# MODULE.net
KiCad netlist of a schematic drawn in Altium Designer
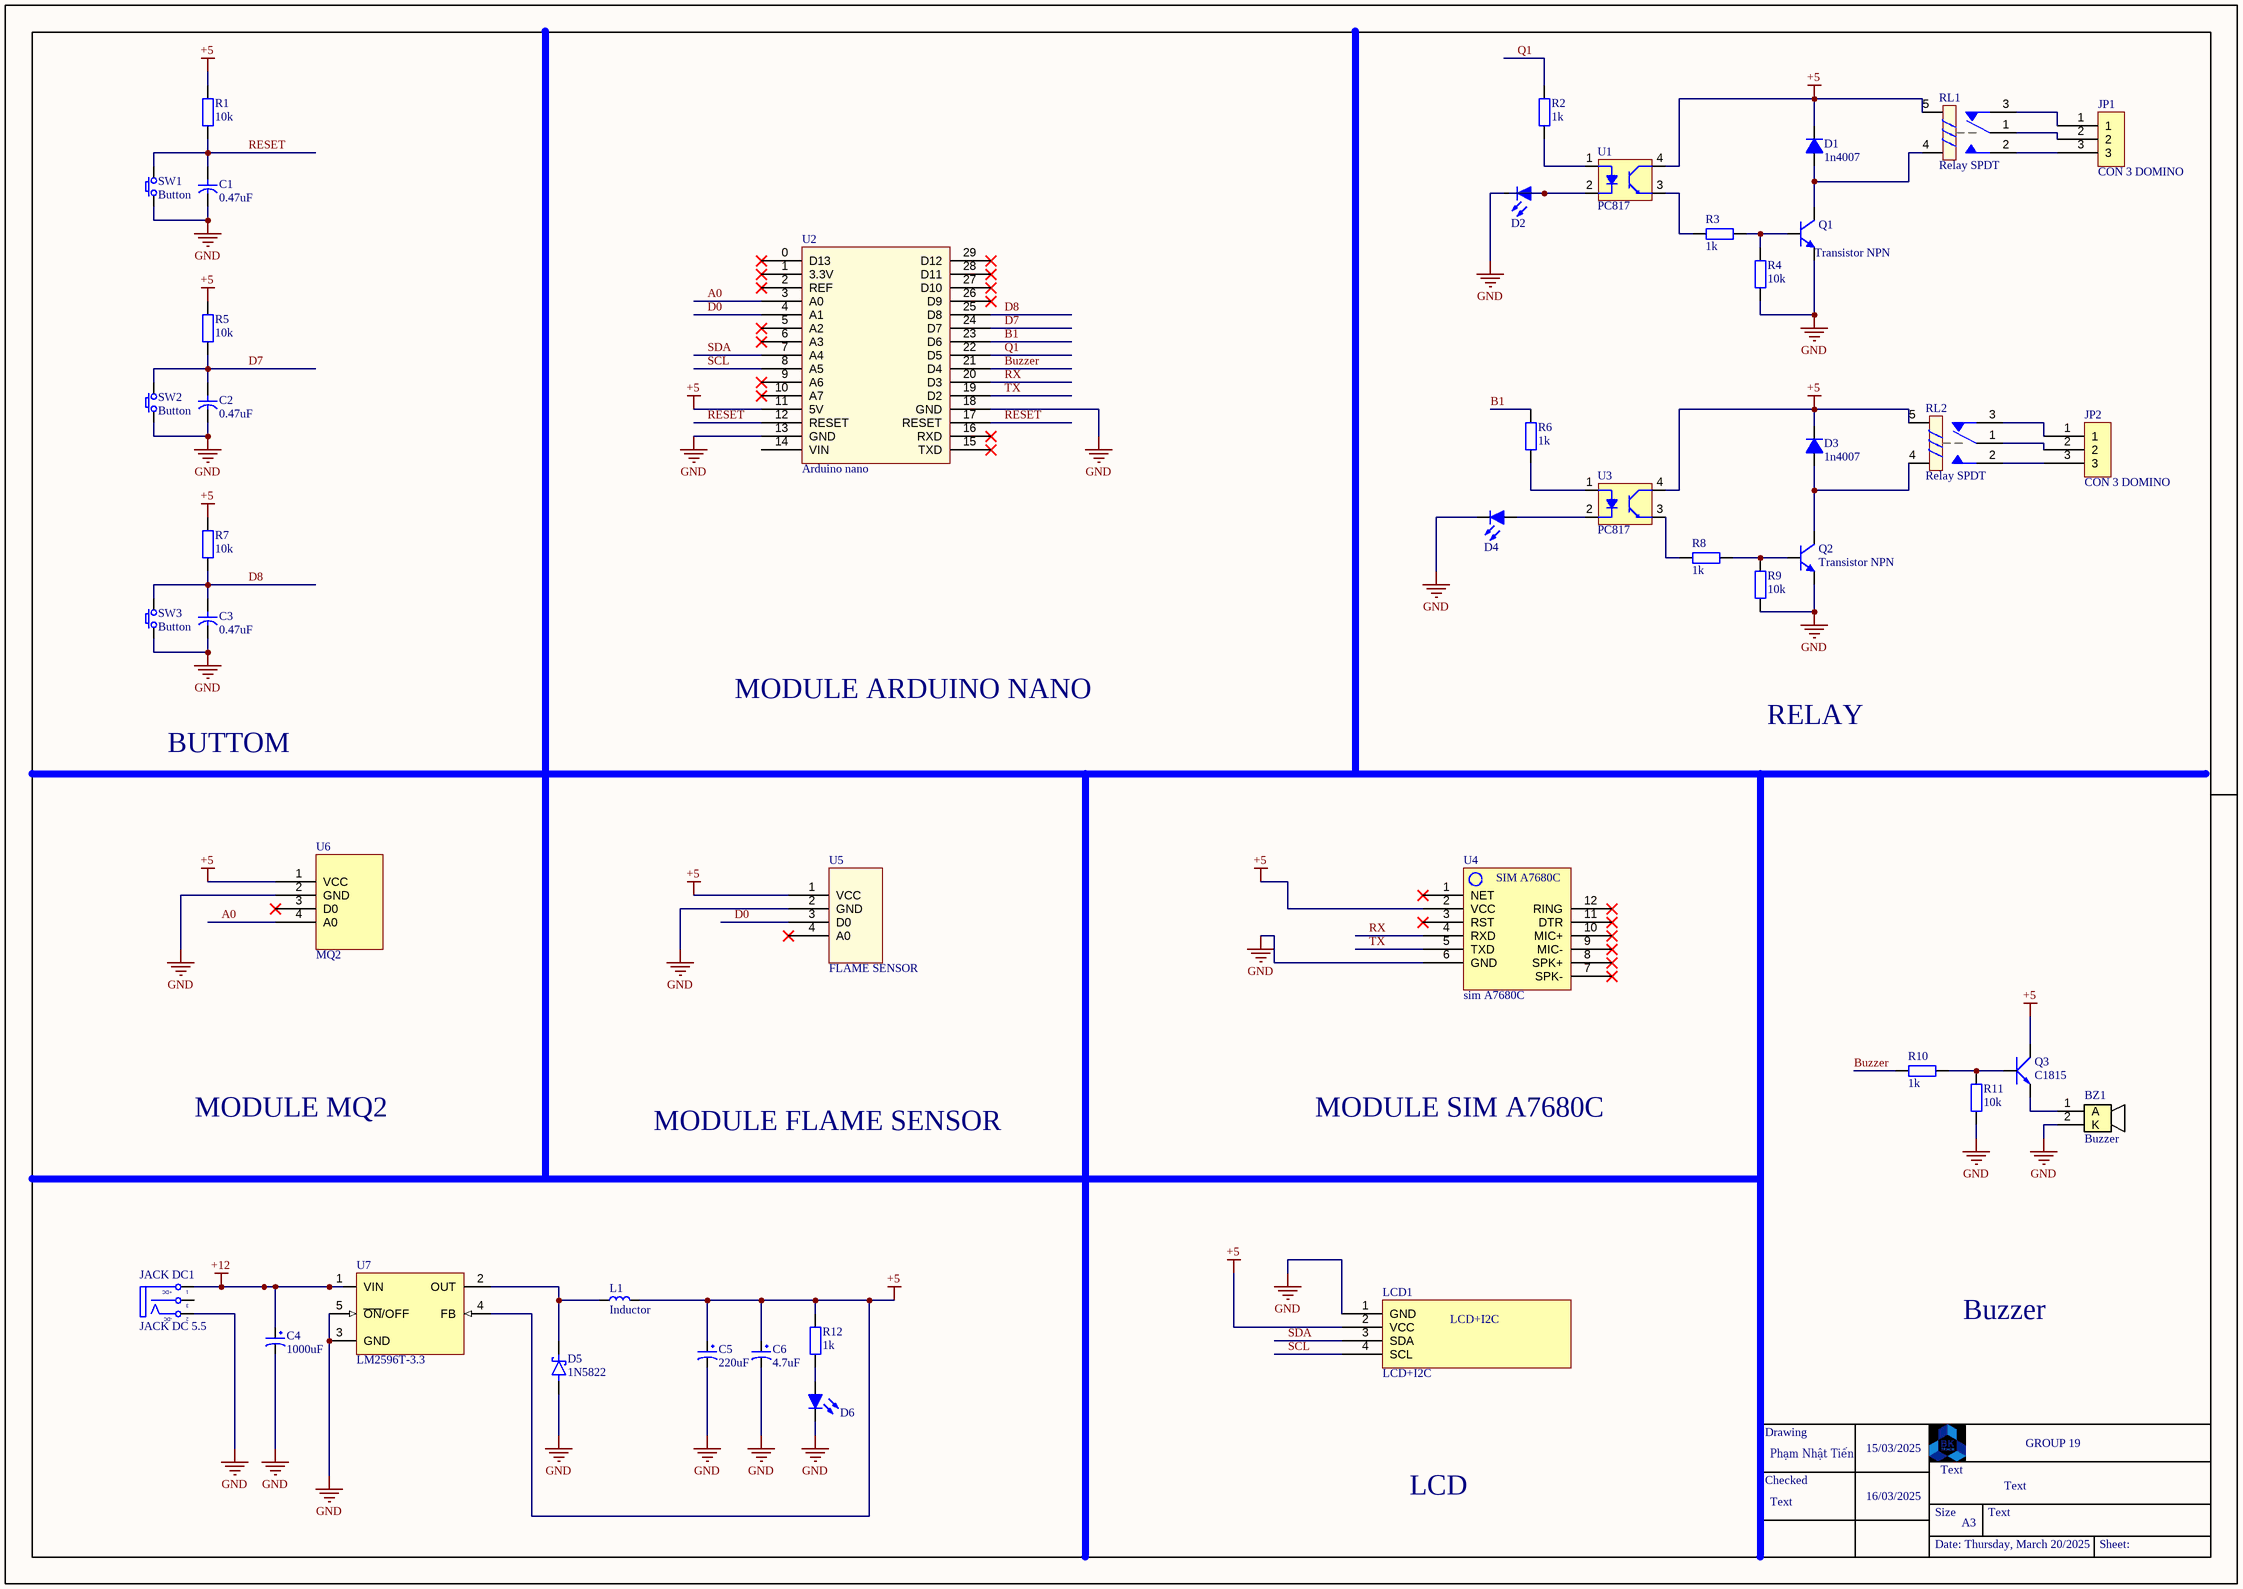
[diagram p0: MODULE.SchDoc]

(export (version "E")
  (design (tool "Eeschema 10.0.6"))
  (components
    (comp (ref "BZ1")
      (value "Buzzer")
      (footprint "BUZZER-2")
      (libsource (lib "chipfc_altium_libs") (part "Buzzer"))
    )
    (comp (ref "C1")
      (value "0.47uF")
      (footprint "CYL/D.250/LS.100")
      (description "Capacitor pol")
      (libsource (lib "chipfc_altium_libs") (part "Capacitor"))
    )
    (comp (ref "C2")
      (value "0.47uF")
      (footprint "CYL/D.250/LS.100")
      (description "Capacitor pol")
      (libsource (lib "chipfc_altium_libs") (part "Capacitor"))
    )
    (comp (ref "C3")
      (value "0.47uF")
      (footprint "CYL/D.250/LS.100")
      (description "Capacitor pol")
      (libsource (lib "chipfc_altium_libs") (part "Capacitor"))
    )
    (comp (ref "C4")
      (value "1000uF")
      (footprint "tu hoa 13mm")
      (description "Cắm")
      (libsource (lib "Altium_Lib_by_KhueNguyenCreator") (part "Tu Hoa 1000uF 50V 13x26"))
    )
    (comp (ref "C5")
      (value "220uF")
      (footprint "tu hoa 10mm")
      (description "Cắm")
      (libsource (lib "Altium_Lib_by_KhueNguyenCreator") (part "Tu Hoa 220uF 50V 10x14"))
    )
    (comp (ref "C6")
      (value "4.7uF")
      (footprint "tu hoa 5mm")
      (description "Cắm")
      (libsource (lib "Altium_Lib_by_KhueNguyenCreator") (part "Tu Hoa 0.47uF 50V 5x11"))
    )
    (comp (ref "D1")
      (value "1n4007")
      (footprint "DIODE 1A")
      (description "Cắm")
      (libsource (lib "Altium_Lib_by_KhueNguyenCreator") (part "Diode 1N4007"))
    )
    (comp (ref "D2")
      (value "Led")
      (footprint "LED 5MM - RED")
      (description "Typical LED")
      (libsource (lib "chipfc_altium_libs") (part "Led"))
    )
    (comp (ref "D3")
      (value "1n4007")
      (footprint "DIODE 1A")
      (description "Cắm")
      (libsource (lib "Altium_Lib_by_KhueNguyenCreator") (part "Diode 1N4007"))
    )
    (comp (ref "D4")
      (value "Led")
      (footprint "LED 5MM - RED")
      (description "Typical LED")
      (libsource (lib "chipfc_altium_libs") (part "Led"))
    )
    (comp (ref "D5") (value "1N5822") (footprint "1N5822") (libsource (lib "TIEN") (part "1N5822")))
    (comp (ref "D6")
      (value "Led")
      (footprint "LED 5MM - RED")
      (description "Typical LED")
      (libsource (lib "chipfc_altium_libs") (part "Led"))
    )
    (comp (ref "JACK DC1")
      (value "JACK DC 5.5")
      (footprint "JACK DC 5.5")
      (libsource (lib "Altium_Lib_by_KhueNguyenCreator") (part "JACK DC 5.5"))
    )
    (comp (ref "JP1")
      (value "CON 3 DOMINO")
      (footprint "CON 3")
      (libsource (lib "TIEN") (part "CON 3 DOMINO"))
    )
    (comp (ref "JP2")
      (value "CON 3 DOMINO")
      (footprint "CON 3")
      (libsource (lib "TIEN") (part "CON 3 DOMINO"))
    )
    (comp (ref "L1")
      (value "Inductor")
      (footprint "L/D9H12")
      (libsource (lib "chipfc_altium_libs") (part "Inductor"))
    )
    (comp (ref "LCD1") (value "LCD+I2C") (footprint "LCD+I2C") (libsource (lib "TIEN") (part "LCD+I2C")))
    (comp (ref "Q1")
      (value "Transistor NPN")
      (footprint "TO-92/W100")
      (description "NPN Bipolar Transistor")
      (libsource (lib "chipfc_altium_libs") (part "Transistor NPN"))
    )
    (comp (ref "Q2")
      (value "Transistor NPN")
      (footprint "TO-92/W100")
      (description "NPN Bipolar Transistor")
      (libsource (lib "chipfc_altium_libs") (part "Transistor NPN"))
    )
    (comp (ref "Q3")
      (value "C1815")
      (footprint "TO92")
      (description "NPN transistor")
      (libsource (lib "Altium_Lib_by_KhueNguyenCreator") (part "Trans C1815 DIP"))
    )
    (comp (ref "R1")
      (value "10k")
      (footprint "tro vach 1/4w")
      (description "Căm")
      (libsource (lib "Altium_Lib_by_KhueNguyenCreator") (part "Tro Vach 1/4W 5% 10k"))
    )
    (comp (ref "R2")
      (value "1k")
      (footprint "tro vach 1/4w")
      (description "Cắm")
      (libsource (lib "Altium_Lib_by_KhueNguyenCreator") (part "Tro Vach 1/4W 5% 1k"))
    )
    (comp (ref "R3")
      (value "1k")
      (footprint "tro vach 1/4w")
      (description "Cắm")
      (libsource (lib "Altium_Lib_by_KhueNguyenCreator") (part "Tro Vach 1/4W 5% 1k"))
    )
    (comp (ref "R4")
      (value "10k")
      (footprint "tro vach 1/4w")
      (description "Cắm")
      (libsource (lib "Altium_Lib_by_KhueNguyenCreator") (part "Tro Vach 1/4W 1% 10k"))
    )
    (comp (ref "R5")
      (value "10k")
      (footprint "tro vach 1/4w")
      (description "Căm")
      (libsource (lib "Altium_Lib_by_KhueNguyenCreator") (part "Tro Vach 1/4W 5% 10k"))
    )
    (comp (ref "R6")
      (value "1k")
      (footprint "tro vach 1/4w")
      (description "Cắm")
      (libsource (lib "Altium_Lib_by_KhueNguyenCreator") (part "Tro Vach 1/4W 5% 1k"))
    )
    (comp (ref "R7")
      (value "10k")
      (footprint "tro vach 1/4w")
      (description "Căm")
      (libsource (lib "Altium_Lib_by_KhueNguyenCreator") (part "Tro Vach 1/4W 5% 10k"))
    )
    (comp (ref "R8")
      (value "1k")
      (footprint "tro vach 1/4w")
      (description "Cắm")
      (libsource (lib "Altium_Lib_by_KhueNguyenCreator") (part "Tro Vach 1/4W 5% 1k"))
    )
    (comp (ref "R9")
      (value "10k")
      (footprint "tro vach 1/4w")
      (description "Cắm")
      (libsource (lib "Altium_Lib_by_KhueNguyenCreator") (part "Tro Vach 1/4W 1% 10k"))
    )
    (comp (ref "R10")
      (value "1k")
      (footprint "tro vach 1/4w")
      (description "Cắm")
      (libsource (lib "Altium_Lib_by_KhueNguyenCreator") (part "Tro Vach 1/4W 5% 1R"))
    )
    (comp (ref "R11")
      (value "10k")
      (footprint "tro vach 1/4w")
      (description "Căm")
      (libsource (lib "Altium_Lib_by_KhueNguyenCreator") (part "Tro Vach 1/4W 5% 10k"))
    )
    (comp (ref "R12")
      (value "1k")
      (footprint "tro vach 1/4w")
      (description "Cắm")
      (libsource (lib "Altium_Lib_by_KhueNguyenCreator") (part "Tro Vach 1/4W 5% 1k"))
    )
    (comp (ref "RL1")
      (value "Relay SPDT")
      (footprint "RL_SPDT_10A")
      (libsource (lib "chipfc_altium_libs") (part "Relay SPDT"))
    )
    (comp (ref "RL2")
      (value "Relay SPDT")
      (footprint "RL_SPDT_10A")
      (libsource (lib "chipfc_altium_libs") (part "Relay SPDT"))
    )
    (comp (ref "SW1")
      (value "Button")
      (footprint "SW/2/DIP")
      (description "Tact switch 2 pin")
      (libsource (lib "chipfc_altium_libs") (part "SW SPST"))
    )
    (comp (ref "SW2")
      (value "Button")
      (footprint "SW/2/DIP")
      (description "Tact switch 2 pin")
      (libsource (lib "chipfc_altium_libs") (part "SW SPST"))
    )
    (comp (ref "SW3")
      (value "Button")
      (footprint "SW/2/DIP")
      (description "Tact switch 2 pin")
      (libsource (lib "chipfc_altium_libs") (part "SW SPST"))
    )
    (comp (ref "U1")
      (value "PC817")
      (footprint "DIP4 - PC817")
      (description "Opto PC817B")
      (libsource (lib "chipfc_altium_libs") (part "PC817"))
    )
    (comp (ref "U2")
      (value "Arduino nano")
      (footprint "Arduino nano")
      (libsource (lib "TIEN") (part "Arduino nano"))
    )
    (comp (ref "U3")
      (value "PC817")
      (footprint "DIP4 - PC817")
      (description "Opto PC817B")
      (libsource (lib "chipfc_altium_libs") (part "PC817"))
    )
    (comp (ref "U4")
      (value "sim A7680C")
      (footprint "SIM A7680C")
      (libsource (lib "TIEN") (part "sim A7680C"))
    )
    (comp (ref "U5")
      (value "FLAME SENSOR")
      (footprint "FLAME SENSOR")
      (libsource (lib "TIEN") (part "FLAME SENSOR"))
    )
    (comp (ref "U6") (value "MQ2") (footprint "MQ2") (libsource (lib "TIEN") (part "MQ2")))
    (comp (ref "U7")
      (value "LM2596T-3.3")
      (footprint "T05D")
      (description "SIMPLE SWITCHER® Power Converter 150 KHz 3A Step-Down Voltage Regulator, 5-pin TO-220")
      (fields (field (name "MANUFACTURER") "National Semiconductor"))
      (libsource (lib "Altium Content Vault") (part "PM-REG-LM2575HVT-12"))
    )
  )
  (nets
    (net (code "1") (name "+5") (class "Default")
      (node (ref "C5") (pin "1") (pinfunction "1_1") (pintype "passive"))
      (node (ref "C6") (pin "1") (pinfunction "1_1") (pintype "passive"))
      (node (ref "D1") (pin "2") (pinfunction "K_2") (pintype "passive"))
      (node (ref "D3") (pin "2") (pinfunction "K_2") (pintype "passive"))
      (node (ref "L1") (pin "2") (pinfunction "2_2") (pintype "passive"))
      (node (ref "LCD1") (pin "2") (pinfunction "VCC_2") (pintype "passive"))
      (node (ref "Q3") (pin "2") (pinfunction "C_2") (pintype "passive"))
      (node (ref "R1") (pin "2") (pinfunction "2_2") (pintype "passive"))
      (node (ref "R12") (pin "2") (pinfunction "2_2") (pintype "passive"))
      (node (ref "R5") (pin "2") (pinfunction "2_2") (pintype "passive"))
      (node (ref "R7") (pin "2") (pinfunction "2_2") (pintype "passive"))
      (node (ref "RL1") (pin "5") (pinfunction "COIL2_5") (pintype "passive"))
      (node (ref "RL2") (pin "5") (pinfunction "COIL2_5") (pintype "passive"))
      (node (ref "U1") (pin "4") (pinfunction "C_4") (pintype "passive"))
      (node (ref "U2") (pin "11") (pinfunction "5V_11") (pintype "passive"))
      (node (ref "U3") (pin "4") (pinfunction "C_4") (pintype "passive"))
      (node (ref "U4") (pin "2") (pinfunction "VCC_2") (pintype "passive"))
      (node (ref "U5") (pin "1") (pinfunction "VCC_1") (pintype "passive"))
      (node (ref "U6") (pin "1") (pinfunction "VCC_1") (pintype "passive"))
      (node (ref "U7") (pin "4") (pinfunction "FB_4") (pintype "input"))
    )
    (net (code "2") (name "+12") (class "Default")
      (node (ref "C4") (pin "1") (pinfunction "1_1") (pintype "passive"))
      (node (ref "JACK DC1") (pin "1") (pinfunction "T_1") (pintype "passive"))
      (node (ref "U7") (pin "1") (pinfunction "VIN_1") (pintype "power_in"))
    )
    (net (code "3") (name "/A0") (class "Default")
      (node (ref "U2") (pin "3") (pinfunction "A0_3") (pintype "passive"))
      (node (ref "U6") (pin "4") (pinfunction "A0_4") (pintype "passive"))
    )
    (net (code "4") (name "/B1") (class "Default")
      (node (ref "R6") (pin "2") (pinfunction "2_2") (pintype "passive"))
      (node (ref "U2") (pin "23") (pinfunction "D6_23") (pintype "passive"))
    )
    (net (code "5") (name "/Buzzer") (class "Default")
      (node (ref "R10") (pin "1") (pinfunction "1_1") (pintype "passive"))
      (node (ref "U2") (pin "21") (pinfunction "D4_21") (pintype "passive"))
    )
    (net (code "6") (name "/D0") (class "Default")
      (node (ref "U2") (pin "4") (pinfunction "A1_4") (pintype "passive"))
      (node (ref "U5") (pin "3") (pinfunction "D0_3") (pintype "passive"))
    )
    (net (code "7") (name "/D7") (class "Default")
      (node (ref "C2") (pin "1") (pinfunction "1_1") (pintype "passive"))
      (node (ref "R5") (pin "1") (pinfunction "1_1") (pintype "passive"))
      (node (ref "SW2") (pin "2") (pinfunction "2_2") (pintype "passive"))
      (node (ref "U2") (pin "24") (pinfunction "D7_24") (pintype "passive"))
    )
    (net (code "8") (name "/D8") (class "Default")
      (node (ref "C3") (pin "1") (pinfunction "1_1") (pintype "passive"))
      (node (ref "R7") (pin "1") (pinfunction "1_1") (pintype "passive"))
      (node (ref "SW3") (pin "2") (pinfunction "2_2") (pintype "passive"))
      (node (ref "U2") (pin "25") (pinfunction "D8_25") (pintype "passive"))
    )
    (net (code "9") (name "/Q1") (class "Default")
      (node (ref "R2") (pin "2") (pinfunction "2_2") (pintype "passive"))
      (node (ref "U2") (pin "22") (pinfunction "D5_22") (pintype "passive"))
    )
    (net (code "10") (name "/RESET") (class "Default")
      (node (ref "C1") (pin "1") (pinfunction "1_1") (pintype "passive"))
      (node (ref "R1") (pin "1") (pinfunction "1_1") (pintype "passive"))
      (node (ref "SW1") (pin "2") (pinfunction "2_2") (pintype "passive"))
      (node (ref "U2") (pin "12") (pinfunction "RESET_12") (pintype "passive"))
      (node (ref "U2") (pin "17") (pinfunction "RESET_17") (pintype "passive"))
    )
    (net (code "11") (name "/RX") (class "Default")
      (node (ref "U2") (pin "20") (pinfunction "D3_20") (pintype "passive"))
      (node (ref "U4") (pin "4") (pinfunction "RXD_4") (pintype "passive"))
    )
    (net (code "12") (name "/SCL") (class "Default")
      (node (ref "LCD1") (pin "4") (pinfunction "SCL_4") (pintype "passive"))
      (node (ref "U2") (pin "8") (pinfunction "A5_8") (pintype "passive"))
    )
    (net (code "13") (name "/SDA") (class "Default")
      (node (ref "LCD1") (pin "3") (pinfunction "SDA_3") (pintype "passive"))
      (node (ref "U2") (pin "7") (pinfunction "A4_7") (pintype "passive"))
    )
    (net (code "14") (name "/TX") (class "Default")
      (node (ref "U2") (pin "19") (pinfunction "D2_19") (pintype "passive"))
      (node (ref "U4") (pin "5") (pinfunction "TXD_5") (pintype "passive"))
    )
    (net (code "15") (name "GND") (class "Default")
      (node (ref "BZ1") (pin "2") (pinfunction "K_2") (pintype "passive"))
      (node (ref "C1") (pin "2") (pinfunction "2_2") (pintype "passive"))
      (node (ref "C2") (pin "2") (pinfunction "2_2") (pintype "passive"))
      (node (ref "C3") (pin "2") (pinfunction "2_2") (pintype "passive"))
      (node (ref "C4") (pin "2") (pinfunction "2_2") (pintype "passive"))
      (node (ref "C5") (pin "2") (pinfunction "2_2") (pintype "passive"))
      (node (ref "C6") (pin "2") (pinfunction "2_2") (pintype "passive"))
      (node (ref "D2") (pin "2") (pinfunction "K_2") (pintype "passive"))
      (node (ref "D4") (pin "2") (pinfunction "K_2") (pintype "passive"))
      (node (ref "D5") (pin "1") (pinfunction "A_1") (pintype "passive"))
      (node (ref "D6") (pin "2") (pinfunction "K_2") (pintype "passive"))
      (node (ref "JACK DC1") (pin "2") (pinfunction "TN_2") (pintype "passive"))
      (node (ref "LCD1") (pin "1") (pinfunction "GND_1") (pintype "passive"))
      (node (ref "Q1") (pin "2") (pinfunction "E_2") (pintype "passive"))
      (node (ref "Q2") (pin "2") (pinfunction "E_2") (pintype "passive"))
      (node (ref "R11") (pin "1") (pinfunction "1_1") (pintype "passive"))
      (node (ref "R4") (pin "1") (pinfunction "1_1") (pintype "passive"))
      (node (ref "R9") (pin "1") (pinfunction "1_1") (pintype "passive"))
      (node (ref "SW1") (pin "1") (pinfunction "1_1") (pintype "passive"))
      (node (ref "SW2") (pin "1") (pinfunction "1_1") (pintype "passive"))
      (node (ref "SW3") (pin "1") (pinfunction "1_1") (pintype "passive"))
      (node (ref "U2") (pin "13") (pinfunction "GND_13") (pintype "passive"))
      (node (ref "U2") (pin "18") (pinfunction "GND_18") (pintype "passive"))
      (node (ref "U4") (pin "6") (pinfunction "GND_6") (pintype "passive"))
      (node (ref "U5") (pin "2") (pinfunction "GND_2") (pintype "passive"))
      (node (ref "U6") (pin "2") (pinfunction "GND_2") (pintype "passive"))
      (node (ref "U7") (pin "3") (pinfunction "GND_3") (pintype "power_in"))
      (node (ref "U7") (pin "5") (pinfunction "~{ON}/OFF_5") (pintype "input"))
    )
    (net (code "16") (name "Net-(BZ1-A)") (class "Default")
      (node (ref "BZ1") (pin "1") (pinfunction "A_1") (pintype "passive"))
      (node (ref "Q3") (pin "1") (pinfunction "E_1") (pintype "passive"))
    )
    (net (code "17") (name "Net-(D1-A)") (class "Default")
      (node (ref "D1") (pin "1") (pinfunction "A_1") (pintype "passive"))
      (node (ref "Q1") (pin "3") (pinfunction "C_3") (pintype "passive"))
      (node (ref "RL1") (pin "4") (pinfunction "COIL1_4") (pintype "passive"))
    )
    (net (code "18") (name "Net-(D2-A)") (class "Default")
      (node (ref "D2") (pin "1") (pinfunction "A_1") (pintype "passive"))
      (node (ref "U1") (pin "2") (pinfunction "K_2") (pintype "passive"))
    )
    (net (code "19") (name "Net-(D3-A)") (class "Default")
      (node (ref "D3") (pin "1") (pinfunction "A_1") (pintype "passive"))
      (node (ref "Q2") (pin "3") (pinfunction "C_3") (pintype "passive"))
      (node (ref "RL2") (pin "4") (pinfunction "COIL1_4") (pintype "passive"))
    )
    (net (code "20") (name "Net-(D4-A)") (class "Default")
      (node (ref "D4") (pin "1") (pinfunction "A_1") (pintype "passive"))
      (node (ref "U3") (pin "2") (pinfunction "K_2") (pintype "passive"))
    )
    (net (code "21") (name "Net-(D5-K)") (class "Default")
      (node (ref "D5") (pin "2") (pinfunction "K_2") (pintype "passive"))
      (node (ref "L1") (pin "1") (pinfunction "1_1") (pintype "passive"))
      (node (ref "U7") (pin "2") (pinfunction "OUT_2") (pintype "power_in"))
    )
    (net (code "22") (name "Net-(D6-A)") (class "Default")
      (node (ref "D6") (pin "1") (pinfunction "A_1") (pintype "passive"))
      (node (ref "R12") (pin "1") (pinfunction "1_1") (pintype "passive"))
    )
    (net (code "23") (name "Net-(Q1-B)") (class "Default")
      (node (ref "Q1") (pin "1") (pinfunction "B_1") (pintype "passive"))
      (node (ref "R3") (pin "2") (pinfunction "2_2") (pintype "passive"))
      (node (ref "R4") (pin "2") (pinfunction "2_2") (pintype "passive"))
    )
    (net (code "24") (name "Net-(Q2-B)") (class "Default")
      (node (ref "Q2") (pin "1") (pinfunction "B_1") (pintype "passive"))
      (node (ref "R8") (pin "2") (pinfunction "2_2") (pintype "passive"))
      (node (ref "R9") (pin "2") (pinfunction "2_2") (pintype "passive"))
    )
    (net (code "25") (name "Net-(Q3-B)") (class "Default")
      (node (ref "Q3") (pin "3") (pinfunction "B_3") (pintype "passive"))
      (node (ref "R10") (pin "2") (pinfunction "2_2") (pintype "passive"))
      (node (ref "R11") (pin "2") (pinfunction "2_2") (pintype "passive"))
    )
    (net (code "26") (name "Net-(RL1-COM)") (class "Default")
      (node (ref "JP1") (pin "2") (pinfunction "2_2") (pintype "passive"))
      (node (ref "RL1") (pin "1") (pinfunction "COM_1") (pintype "passive"))
    )
    (net (code "27") (name "Net-(RL1-NC)") (class "Default")
      (node (ref "JP1") (pin "1") (pinfunction "1_1") (pintype "passive"))
      (node (ref "RL1") (pin "3") (pinfunction "NC_3") (pintype "passive"))
    )
    (net (code "28") (name "Net-(RL1-NO)") (class "Default")
      (node (ref "JP1") (pin "3") (pinfunction "3_3") (pintype "passive"))
      (node (ref "RL1") (pin "2") (pinfunction "NO_2") (pintype "passive"))
    )
    (net (code "29") (name "Net-(RL2-COM)") (class "Default")
      (node (ref "JP2") (pin "2") (pinfunction "2_2") (pintype "passive"))
      (node (ref "RL2") (pin "1") (pinfunction "COM_1") (pintype "passive"))
    )
    (net (code "30") (name "Net-(RL2-NC)") (class "Default")
      (node (ref "JP2") (pin "1") (pinfunction "1_1") (pintype "passive"))
      (node (ref "RL2") (pin "3") (pinfunction "NC_3") (pintype "passive"))
    )
    (net (code "31") (name "Net-(RL2-NO)") (class "Default")
      (node (ref "JP2") (pin "3") (pinfunction "3_3") (pintype "passive"))
      (node (ref "RL2") (pin "2") (pinfunction "NO_2") (pintype "passive"))
    )
    (net (code "32") (name "Net-(U1-A)") (class "Default")
      (node (ref "R2") (pin "1") (pinfunction "1_1") (pintype "passive"))
      (node (ref "U1") (pin "1") (pinfunction "A_1") (pintype "passive"))
    )
    (net (code "33") (name "Net-(U1-E)") (class "Default")
      (node (ref "R3") (pin "1") (pinfunction "1_1") (pintype "passive"))
      (node (ref "U1") (pin "3") (pinfunction "E_3") (pintype "passive"))
    )
    (net (code "34") (name "Net-(U3-A)") (class "Default")
      (node (ref "R6") (pin "1") (pinfunction "1_1") (pintype "passive"))
      (node (ref "U3") (pin "1") (pinfunction "A_1") (pintype "passive"))
    )
    (net (code "35") (name "Net-(U3-E)") (class "Default")
      (node (ref "R8") (pin "1") (pinfunction "1_1") (pintype "passive"))
      (node (ref "U3") (pin "3") (pinfunction "E_3") (pintype "passive"))
    )
    (net (code "36") (name "unconnected-(JACK DC1-S-Pad3)") (class "Default")
      (node (ref "JACK DC1") (pin "3") (pinfunction "S_3") (pintype "power_in"))
    )
    (net (code "37") (name "unconnected-(U2-3.3V-Pad1)") (class "Default")
      (node (ref "U2") (pin "1") (pinfunction "3.3V_1") (pintype "passive+no_connect"))
    )
    (net (code "38") (name "unconnected-(U2-A2-Pad5)") (class "Default")
      (node (ref "U2") (pin "5") (pinfunction "A2_5") (pintype "passive+no_connect"))
    )
    (net (code "39") (name "unconnected-(U2-A3-Pad6)") (class "Default")
      (node (ref "U2") (pin "6") (pinfunction "A3_6") (pintype "passive+no_connect"))
    )
    (net (code "40") (name "unconnected-(U2-A6-Pad9)") (class "Default")
      (node (ref "U2") (pin "9") (pinfunction "A6_9") (pintype "passive+no_connect"))
    )
    (net (code "41") (name "unconnected-(U2-A7-Pad10)") (class "Default")
      (node (ref "U2") (pin "10") (pinfunction "A7_10") (pintype "passive+no_connect"))
    )
    (net (code "42") (name "unconnected-(U2-D9-Pad26)") (class "Default")
      (node (ref "U2") (pin "26") (pinfunction "D9_26") (pintype "passive+no_connect"))
    )
    (net (code "43") (name "unconnected-(U2-D10-Pad27)") (class "Default")
      (node (ref "U2") (pin "27") (pinfunction "D10_27") (pintype "passive+no_connect"))
    )
    (net (code "44") (name "unconnected-(U2-D11-Pad28)") (class "Default")
      (node (ref "U2") (pin "28") (pinfunction "D11_28") (pintype "passive+no_connect"))
    )
    (net (code "45") (name "unconnected-(U2-D12-Pad29)") (class "Default")
      (node (ref "U2") (pin "29") (pinfunction "D12_29") (pintype "passive+no_connect"))
    )
    (net (code "46") (name "unconnected-(U2-D13-Pad0)") (class "Default")
      (node (ref "U2") (pin "0") (pinfunction "D13_0") (pintype "passive+no_connect"))
    )
    (net (code "47") (name "unconnected-(U2-REF-Pad2)") (class "Default")
      (node (ref "U2") (pin "2") (pinfunction "REF_2") (pintype "passive+no_connect"))
    )
    (net (code "48") (name "unconnected-(U2-RXD-Pad16)") (class "Default")
      (node (ref "U2") (pin "16") (pinfunction "RXD_16") (pintype "passive+no_connect"))
    )
    (net (code "49") (name "unconnected-(U2-TXD-Pad15)") (class "Default")
      (node (ref "U2") (pin "15") (pinfunction "TXD_15") (pintype "passive+no_connect"))
    )
    (net (code "50") (name "unconnected-(U2-VIN-Pad14)") (class "Default")
      (node (ref "U2") (pin "14") (pinfunction "VIN_14") (pintype "passive"))
    )
    (net (code "51") (name "unconnected-(U4-DTR-Pad11)") (class "Default")
      (node (ref "U4") (pin "11") (pinfunction "DTR_11") (pintype "passive+no_connect"))
    )
    (net (code "52") (name "unconnected-(U4-MIC+-Pad10)") (class "Default")
      (node (ref "U4") (pin "10") (pinfunction "MIC+_10") (pintype "passive+no_connect"))
    )
    (net (code "53") (name "unconnected-(U4-MIC--Pad9)") (class "Default")
      (node (ref "U4") (pin "9") (pinfunction "MIC-_9") (pintype "passive+no_connect"))
    )
    (net (code "54") (name "unconnected-(U4-NET-Pad1)") (class "Default")
      (node (ref "U4") (pin "1") (pinfunction "NET_1") (pintype "passive+no_connect"))
    )
    (net (code "55") (name "unconnected-(U4-RING-Pad12)") (class "Default")
      (node (ref "U4") (pin "12") (pinfunction "RING_12") (pintype "passive+no_connect"))
    )
    (net (code "56") (name "unconnected-(U4-RST-Pad3)") (class "Default")
      (node (ref "U4") (pin "3") (pinfunction "RST_3") (pintype "passive+no_connect"))
    )
    (net (code "57") (name "unconnected-(U4-SPK+-Pad8)") (class "Default")
      (node (ref "U4") (pin "8") (pinfunction "SPK+_8") (pintype "passive+no_connect"))
    )
    (net (code "58") (name "unconnected-(U4-SPK--Pad7)") (class "Default")
      (node (ref "U4") (pin "7") (pinfunction "SPK-_7") (pintype "passive+no_connect"))
    )
    (net (code "59") (name "unconnected-(U5-A0-Pad4)") (class "Default")
      (node (ref "U5") (pin "4") (pinfunction "A0_4") (pintype "passive+no_connect"))
    )
    (net (code "60") (name "unconnected-(U6-D0-Pad3)") (class "Default")
      (node (ref "U6") (pin "3") (pinfunction "D0_3") (pintype "passive+no_connect"))
    )
  )
)
